# WCH_TOUCH_Kit_EX002.net
KiCad netlist of a schematic drawn in Altium Designer
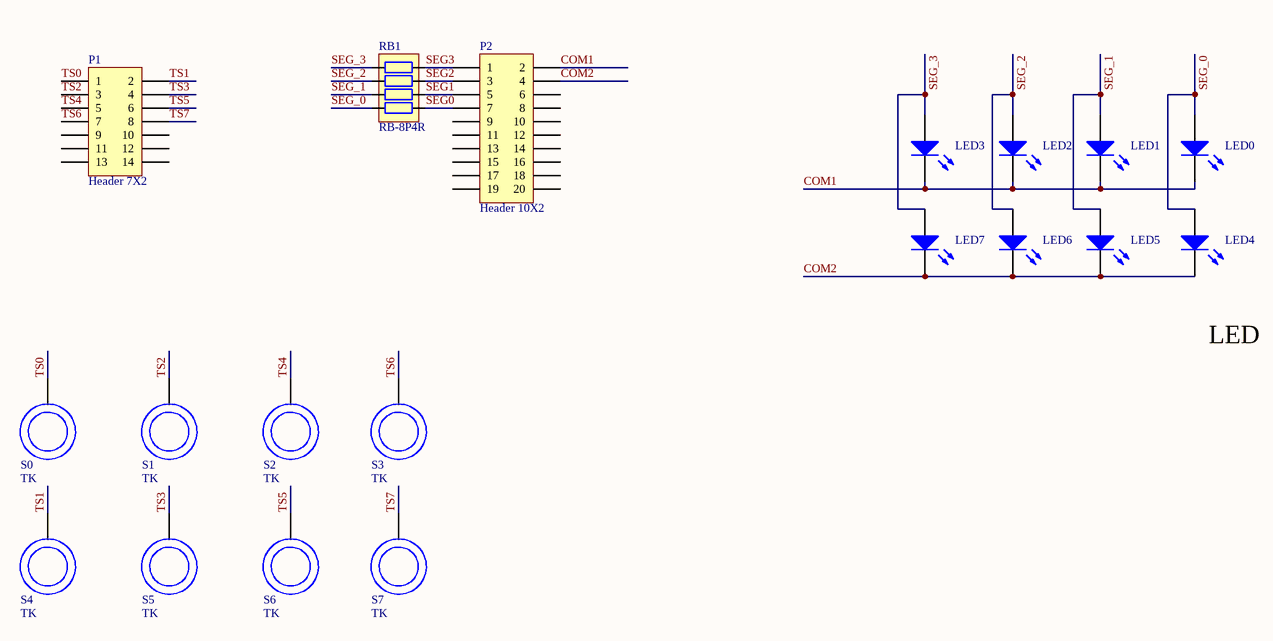
[diagram p0: WCH_TOUCH_Kit_EX002.SchDoc]

(export (version "E")
  (design (tool "Eeschema 10.0.6"))
  (components
    (comp (ref "LED0")
      (value "~")
      (footprint "LED0805-RD_EH")
      (description "Typical BLUE SiC LED")
      (fields (field (name "PUBLISHER") "Altium Limited"))
      (libsource (lib "Miscellaneous Devices") (part "LED3"))
    )
    (comp (ref "LED1")
      (value "~")
      (footprint "LED0805-RD_EH")
      (description "Typical BLUE SiC LED")
      (fields (field (name "PUBLISHER") "Altium Limited"))
      (libsource (lib "Miscellaneous Devices") (part "LED3"))
    )
    (comp (ref "LED2")
      (value "~")
      (footprint "LED0805-RD_EH")
      (description "Typical BLUE SiC LED")
      (fields (field (name "PUBLISHER") "Altium Limited"))
      (libsource (lib "Miscellaneous Devices") (part "LED3"))
    )
    (comp (ref "LED3")
      (value "~")
      (footprint "LED0805-RD_EH")
      (description "Typical BLUE SiC LED")
      (fields (field (name "PUBLISHER") "Altium Limited"))
      (libsource (lib "Miscellaneous Devices") (part "LED3"))
    )
    (comp (ref "LED4")
      (value "~")
      (footprint "LED0805-RD_EH")
      (description "Typical BLUE SiC LED")
      (fields (field (name "PUBLISHER") "Altium Limited"))
      (libsource (lib "Miscellaneous Devices") (part "LED3"))
    )
    (comp (ref "LED5")
      (value "~")
      (footprint "LED0805-RD_EH")
      (description "Typical BLUE SiC LED")
      (fields (field (name "PUBLISHER") "Altium Limited"))
      (libsource (lib "Miscellaneous Devices") (part "LED3"))
    )
    (comp (ref "LED6")
      (value "~")
      (footprint "LED0805-RD_EH")
      (description "Typical BLUE SiC LED")
      (fields (field (name "PUBLISHER") "Altium Limited"))
      (libsource (lib "Miscellaneous Devices") (part "LED3"))
    )
    (comp (ref "LED7")
      (value "~")
      (footprint "LED0805-RD_EH")
      (description "Typical BLUE SiC LED")
      (fields (field (name "PUBLISHER") "Altium Limited"))
      (libsource (lib "Miscellaneous Devices") (part "LED3"))
    )
    (comp (ref "P1")
      (value "Header 7X2")
      (footprint "HDR-TH_14P-P2.54-H-F-R2-C10-W8.5")
      (description "Header, 7-Pin, Dual row")
      (fields (field (name "PUBLISHER") "Altium Limited"))
      (libsource (lib "Miscellaneous Connectors") (part "Header 7X2"))
    )
    (comp (ref "P2")
      (value "Header 10X2")
      (footprint "HDR-TH_20P-P2.54-H-F-R2-C10-W8.5")
      (description "Header, 10-Pin, Dual row")
      (fields (field (name "PUBLISHER") "Altium Limited"))
      (libsource (lib "Miscellaneous Connectors") (part "Header 10X2"))
    )
    (comp (ref "RB1")
      (value "RB-8P4R")
      (footprint "RCA-8P4R-0603")
      (description "贴片网络排阻")
      (libsource (lib "wch_sch_others") (part "RB-8P4R"))
    )
    (comp (ref "S0")
      (value "TK")
      (footprint "TOUCHKEY-12mm-S")
      (libsource (lib "SOC MCU封装库 V0.21-22.04.19") (part "TK"))
    )
    (comp (ref "S1")
      (value "TK")
      (footprint "TOUCHKEY-12mm-S")
      (libsource (lib "SOC MCU封装库 V0.21-22.04.19") (part "TK"))
    )
    (comp (ref "S2")
      (value "TK")
      (footprint "TOUCHKEY-12mm-S")
      (libsource (lib "SOC MCU封装库 V0.21-22.04.19") (part "TK"))
    )
    (comp (ref "S3")
      (value "TK")
      (footprint "TOUCHKEY-12mm-S")
      (libsource (lib "SOC MCU封装库 V0.21-22.04.19") (part "TK"))
    )
    (comp (ref "S4")
      (value "TK")
      (footprint "TOUCHKEY-12mm-S")
      (libsource (lib "SOC MCU封装库 V0.21-22.04.19") (part "TK"))
    )
    (comp (ref "S5")
      (value "TK")
      (footprint "TOUCHKEY-12mm-S")
      (libsource (lib "SOC MCU封装库 V0.21-22.04.19") (part "TK"))
    )
    (comp (ref "S6")
      (value "TK")
      (footprint "TOUCHKEY-12mm-S")
      (libsource (lib "SOC MCU封装库 V0.21-22.04.19") (part "TK"))
    )
    (comp (ref "S7")
      (value "TK")
      (footprint "TOUCHKEY-12mm-S")
      (libsource (lib "SOC MCU封装库 V0.21-22.04.19") (part "TK"))
    )
  )
  (nets
    (net (code "1") (name "/COM1") (class "Default")
      (node (ref "LED0") (pin "2") (pinfunction "K_2") (pintype "passive"))
      (node (ref "LED1") (pin "2") (pinfunction "K_2") (pintype "passive"))
      (node (ref "LED2") (pin "2") (pinfunction "K_2") (pintype "passive"))
      (node (ref "LED3") (pin "2") (pinfunction "K_2") (pintype "passive"))
      (node (ref "P2") (pin "2") (pinfunction "2_2") (pintype "passive"))
    )
    (net (code "2") (name "/COM2") (class "Default")
      (node (ref "LED4") (pin "2") (pinfunction "K_2") (pintype "passive"))
      (node (ref "LED5") (pin "2") (pinfunction "K_2") (pintype "passive"))
      (node (ref "LED6") (pin "2") (pinfunction "K_2") (pintype "passive"))
      (node (ref "LED7") (pin "2") (pinfunction "K_2") (pintype "passive"))
      (node (ref "P2") (pin "4") (pinfunction "4_4") (pintype "passive"))
    )
    (net (code "3") (name "/SEG0") (class "Default")
      (node (ref "P2") (pin "7") (pinfunction "7_7") (pintype "passive"))
      (node (ref "RB1") (pin "4") (pinfunction "4_4") (pintype "passive"))
    )
    (net (code "4") (name "/SEG1") (class "Default")
      (node (ref "P2") (pin "5") (pinfunction "5_5") (pintype "passive"))
      (node (ref "RB1") (pin "3") (pinfunction "3_3") (pintype "passive"))
    )
    (net (code "5") (name "/SEG2") (class "Default")
      (node (ref "P2") (pin "3") (pinfunction "3_3") (pintype "passive"))
      (node (ref "RB1") (pin "2") (pinfunction "2_2") (pintype "passive"))
    )
    (net (code "6") (name "/SEG3") (class "Default")
      (node (ref "P2") (pin "1") (pinfunction "1_1") (pintype "passive"))
      (node (ref "RB1") (pin "1") (pinfunction "1_1") (pintype "passive"))
    )
    (net (code "7") (name "/SEG_0") (class "Default")
      (node (ref "LED0") (pin "1") (pinfunction "A_1") (pintype "passive"))
      (node (ref "LED4") (pin "1") (pinfunction "A_1") (pintype "passive"))
      (node (ref "RB1") (pin "5") (pinfunction "5_5") (pintype "passive"))
    )
    (net (code "8") (name "/SEG_1") (class "Default")
      (node (ref "LED1") (pin "1") (pinfunction "A_1") (pintype "passive"))
      (node (ref "LED5") (pin "1") (pinfunction "A_1") (pintype "passive"))
      (node (ref "RB1") (pin "6") (pinfunction "6_6") (pintype "passive"))
    )
    (net (code "9") (name "/SEG_2") (class "Default")
      (node (ref "LED2") (pin "1") (pinfunction "A_1") (pintype "passive"))
      (node (ref "LED6") (pin "1") (pinfunction "A_1") (pintype "passive"))
      (node (ref "RB1") (pin "7") (pinfunction "7_7") (pintype "passive"))
    )
    (net (code "10") (name "/SEG_3") (class "Default")
      (node (ref "LED3") (pin "1") (pinfunction "A_1") (pintype "passive"))
      (node (ref "LED7") (pin "1") (pinfunction "A_1") (pintype "passive"))
      (node (ref "RB1") (pin "8") (pinfunction "8_8") (pintype "passive"))
    )
    (net (code "11") (name "/TS0") (class "Default")
      (node (ref "P1") (pin "1") (pinfunction "1_1") (pintype "passive"))
      (node (ref "S0") (pin "1") (pintype "passive"))
    )
    (net (code "12") (name "/TS1") (class "Default")
      (node (ref "P1") (pin "2") (pinfunction "2_2") (pintype "passive"))
      (node (ref "S4") (pin "1") (pintype "passive"))
    )
    (net (code "13") (name "/TS2") (class "Default")
      (node (ref "P1") (pin "3") (pinfunction "3_3") (pintype "passive"))
      (node (ref "S1") (pin "1") (pintype "passive"))
    )
    (net (code "14") (name "/TS3") (class "Default")
      (node (ref "P1") (pin "4") (pinfunction "4_4") (pintype "passive"))
      (node (ref "S5") (pin "1") (pintype "passive"))
    )
    (net (code "15") (name "/TS4") (class "Default")
      (node (ref "P1") (pin "5") (pinfunction "5_5") (pintype "passive"))
      (node (ref "S2") (pin "1") (pintype "passive"))
    )
    (net (code "16") (name "/TS5") (class "Default")
      (node (ref "P1") (pin "6") (pinfunction "6_6") (pintype "passive"))
      (node (ref "S6") (pin "1") (pintype "passive"))
    )
    (net (code "17") (name "/TS6") (class "Default")
      (node (ref "P1") (pin "7") (pinfunction "7_7") (pintype "passive"))
      (node (ref "S3") (pin "1") (pintype "passive"))
    )
    (net (code "18") (name "/TS7") (class "Default")
      (node (ref "P1") (pin "8") (pinfunction "8_8") (pintype "passive"))
      (node (ref "S7") (pin "1") (pintype "passive"))
    )
    (net (code "19") (name "unconnected-(P1-Pad9)") (class "Default")
      (node (ref "P1") (pin "9") (pinfunction "9_9") (pintype "passive"))
    )
    (net (code "20") (name "unconnected-(P1-Pad10)") (class "Default")
      (node (ref "P1") (pin "10") (pinfunction "10_10") (pintype "passive"))
    )
    (net (code "21") (name "unconnected-(P1-Pad11)") (class "Default")
      (node (ref "P1") (pin "11") (pinfunction "11_11") (pintype "passive"))
    )
    (net (code "22") (name "unconnected-(P1-Pad12)") (class "Default")
      (node (ref "P1") (pin "12") (pinfunction "12_12") (pintype "passive"))
    )
    (net (code "23") (name "unconnected-(P1-Pad13)") (class "Default")
      (node (ref "P1") (pin "13") (pinfunction "13_13") (pintype "passive"))
    )
    (net (code "24") (name "unconnected-(P1-Pad14)") (class "Default")
      (node (ref "P1") (pin "14") (pinfunction "14_14") (pintype "passive"))
    )
    (net (code "25") (name "unconnected-(P2-Pad6)") (class "Default")
      (node (ref "P2") (pin "6") (pinfunction "6_6") (pintype "passive"))
    )
    (net (code "26") (name "unconnected-(P2-Pad8)") (class "Default")
      (node (ref "P2") (pin "8") (pinfunction "8_8") (pintype "passive"))
    )
    (net (code "27") (name "unconnected-(P2-Pad9)") (class "Default")
      (node (ref "P2") (pin "9") (pinfunction "9_9") (pintype "passive"))
    )
    (net (code "28") (name "unconnected-(P2-Pad10)") (class "Default")
      (node (ref "P2") (pin "10") (pinfunction "10_10") (pintype "passive"))
    )
    (net (code "29") (name "unconnected-(P2-Pad11)") (class "Default")
      (node (ref "P2") (pin "11") (pinfunction "11_11") (pintype "passive"))
    )
    (net (code "30") (name "unconnected-(P2-Pad12)") (class "Default")
      (node (ref "P2") (pin "12") (pinfunction "12_12") (pintype "passive"))
    )
    (net (code "31") (name "unconnected-(P2-Pad13)") (class "Default")
      (node (ref "P2") (pin "13") (pinfunction "13_13") (pintype "passive"))
    )
    (net (code "32") (name "unconnected-(P2-Pad14)") (class "Default")
      (node (ref "P2") (pin "14") (pinfunction "14_14") (pintype "passive"))
    )
    (net (code "33") (name "unconnected-(P2-Pad15)") (class "Default")
      (node (ref "P2") (pin "15") (pinfunction "15_15") (pintype "passive"))
    )
    (net (code "34") (name "unconnected-(P2-Pad16)") (class "Default")
      (node (ref "P2") (pin "16") (pinfunction "16_16") (pintype "passive"))
    )
    (net (code "35") (name "unconnected-(P2-Pad17)") (class "Default")
      (node (ref "P2") (pin "17") (pinfunction "17_17") (pintype "passive"))
    )
    (net (code "36") (name "unconnected-(P2-Pad18)") (class "Default")
      (node (ref "P2") (pin "18") (pinfunction "18_18") (pintype "passive"))
    )
    (net (code "37") (name "unconnected-(P2-Pad19)") (class "Default")
      (node (ref "P2") (pin "19") (pinfunction "19_19") (pintype "passive"))
    )
    (net (code "38") (name "unconnected-(P2-Pad20)") (class "Default")
      (node (ref "P2") (pin "20") (pinfunction "20_20") (pintype "passive"))
    )
  )
)
